# ButtonPanel.net
KiCad netlist of a schematic drawn in Altium Designer
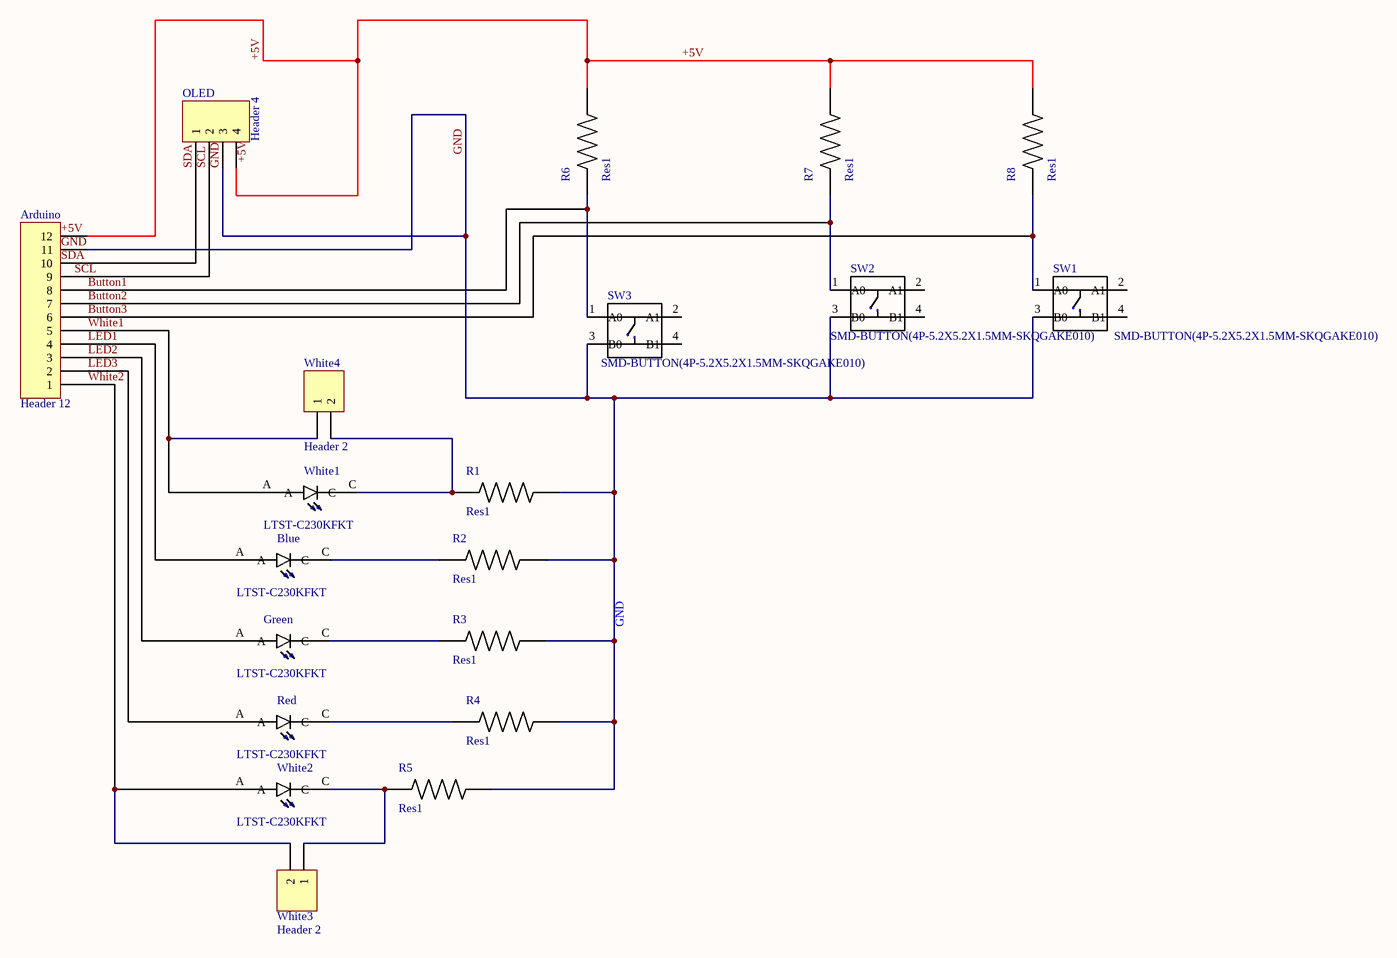
[diagram p0: ButtonPanel.SchDoc]

(export (version "E")
  (design (tool "Eeschema 10.0.6"))
  (components
    (comp (ref "Arduino")
      (value "Header 12")
      (footprint "HDR1X12")
      (description "Header, 12-Pin")
      (fields (field (name "PUBLISHER") "Altium Limited"))
      (libsource (lib "Miscellaneous Connectors") (part "Header 12"))
    )
    (comp (ref "Blue")
      (value "LTST-C230KFKT")
      (footprint "*LEDC3216X110_LTST-C230KFKT(Primary)")
      (description "LED; SMD; 1206; orange; 45-90mcd; 3.2x1.6x1.1mm; 130Â°; 2Ã·2.4V; 20mA")
      (fields (field (name "MF") "Lite-On Inc."))
      (libsource (lib "LTST-C230KFKT") (part "LTST-C230KFKT"))
    )
    (comp (ref "Green")
      (value "LTST-C230KFKT")
      (footprint "*LEDC3216X110_LTST-C230KFKT(Primary)")
      (description "LED; SMD; 1206; orange; 45-90mcd; 3.2x1.6x1.1mm; 130Â°; 2Ã·2.4V; 20mA")
      (fields (field (name "MF") "Lite-On Inc."))
      (libsource (lib "LTST-C230KFKT") (part "LTST-C230KFKT"))
    )
    (comp (ref "OLED")
      (value "Header 4")
      (footprint "HDR1X4")
      (description "Header, 4-Pin")
      (fields (field (name "PUBLISHER") "Altium Limited"))
      (libsource (lib "Miscellaneous Connectors") (part "Header 4"))
    )
    (comp (ref "R1")
      (value "Res1")
      (footprint "*RESC3116X65N")
      (description "RES SMD 330 OHM 0.5% 1/4W 1206")
      (fields (field (name "MF") "Yageo") (field (name "MP") "RT1206DRE07330RL"))
      (libsource (lib "RT1206DRE07330RL") (part "RT1206DRE07330RL"))
    )
    (comp (ref "R2")
      (value "Res1")
      (footprint "*RESC3116X65N")
      (description "RES SMD 330 OHM 0.5% 1/4W 1206")
      (fields (field (name "MF") "Yageo") (field (name "MP") "RT1206DRE07330RL"))
      (libsource (lib "RT1206DRE07330RL") (part "RT1206DRE07330RL"))
    )
    (comp (ref "R3")
      (value "Res1")
      (footprint "*RESC3116X65N")
      (description "RES SMD 330 OHM 0.5% 1/4W 1206")
      (fields (field (name "MF") "Yageo") (field (name "MP") "RT1206DRE07330RL"))
      (libsource (lib "RT1206DRE07330RL") (part "RT1206DRE07330RL"))
    )
    (comp (ref "R4")
      (value "Res1")
      (footprint "*RESC3116X65N")
      (description "RES SMD 330 OHM 0.5% 1/4W 1206")
      (fields (field (name "MF") "Yageo") (field (name "MP") "RT1206DRE07330RL"))
      (libsource (lib "RT1206DRE07330RL") (part "RT1206DRE07330RL"))
    )
    (comp (ref "R5")
      (value "Res1")
      (footprint "*RESC3116X65N")
      (description "RES SMD 330 OHM 0.5% 1/4W 1206")
      (fields (field (name "MF") "Yageo") (field (name "MP") "RT1206DRE07330RL"))
      (libsource (lib "RT1206DRE07330RL") (part "RT1206DRE07330RL"))
    )
    (comp (ref "R6")
      (value "Res1")
      (footprint "*RESC3116X65N")
      (description "RES SMD 10K OHM 0.5% 0.4W 1206")
      (fields (field (name "MF") "Vishay") (field (name "MP") "MCA1206MD1002DP500"))
      (libsource (lib "MCA1206MD1002DP500") (part "MCA1206MD1002DP500"))
    )
    (comp (ref "R7")
      (value "Res1")
      (footprint "*RESC3116X65N")
      (description "RES SMD 10K OHM 0.5% 0.4W 1206")
      (fields (field (name "MF") "Vishay") (field (name "MP") "MCA1206MD1002DP500"))
      (libsource (lib "MCA1206MD1002DP500") (part "MCA1206MD1002DP500"))
    )
    (comp (ref "R8")
      (value "Res1")
      (footprint "*RESC3116X65N")
      (description "RES SMD 10K OHM 0.5% 0.4W 1206")
      (fields (field (name "MF") "Vishay") (field (name "MP") "MCA1206MD1002DP500"))
      (libsource (lib "MCA1206MD1002DP500") (part "MCA1206MD1002DP500"))
    )
    (comp (ref "Red")
      (value "LTST-C230KFKT")
      (footprint "*LEDC3216X110_LTST-C230KFKT(Primary)")
      (description "LED; SMD; 1206; orange; 45-90mcd; 3.2x1.6x1.1mm; 130Â°; 2Ã·2.4V; 20mA")
      (fields (field (name "MF") "Lite-On Inc."))
      (libsource (lib "LTST-C230KFKT") (part "LTST-C230KFKT"))
    )
    (comp (ref "SW1")
      (value "SMD-BUTTON(4P-5.2X5.2X1.5MM-SKQGAKE010)")
      (footprint "*SW4-SMD-5.2X5.2X1.5MM")
      (description "Switch Tactile N.O. SPST Button Gull Wing 0.05A 12VDC 3.43N SMD T/R")
      (fields (field (name "MF") "ALPS") (field (name "MP") "SKQGAKE010"))
      (libsource (lib "SMD-BUTTON_4P-5.2X5.2X1.5MM-SKQGAKE010_") (part "SMD-BUTTON(4P-5.2X5.2X1.5MM-SKQGAKE010)"))
    )
    (comp (ref "SW2")
      (value "SMD-BUTTON(4P-5.2X5.2X1.5MM-SKQGAKE010)")
      (footprint "*SW4-SMD-5.2X5.2X1.5MM")
      (description "Switch Tactile N.O. SPST Button Gull Wing 0.05A 12VDC 3.43N SMD T/R")
      (fields (field (name "MF") "ALPS") (field (name "MP") "SKQGAKE010"))
      (libsource (lib "SMD-BUTTON_4P-5.2X5.2X1.5MM-SKQGAKE010_") (part "SMD-BUTTON(4P-5.2X5.2X1.5MM-SKQGAKE010)"))
    )
    (comp (ref "SW3")
      (value "SMD-BUTTON(4P-5.2X5.2X1.5MM-SKQGAKE010)")
      (footprint "*SW4-SMD-5.2X5.2X1.5MM")
      (description "Switch Tactile N.O. SPST Button Gull Wing 0.05A 12VDC 3.43N SMD T/R")
      (fields (field (name "MF") "ALPS") (field (name "MP") "SKQGAKE010"))
      (libsource (lib "SMD-BUTTON_4P-5.2X5.2X1.5MM-SKQGAKE010_") (part "SMD-BUTTON(4P-5.2X5.2X1.5MM-SKQGAKE010)"))
    )
    (comp (ref "White1")
      (value "LTST-C230KFKT")
      (footprint "*LEDC3216X110_LTST-C230KFKT(Primary)")
      (description "LED; SMD; 1206; orange; 45-90mcd; 3.2x1.6x1.1mm; 130Â°; 2Ã·2.4V; 20mA")
      (fields (field (name "MF") "Lite-On Inc."))
      (libsource (lib "LTST-C230KFKT") (part "LTST-C230KFKT"))
    )
    (comp (ref "White2")
      (value "LTST-C230KFKT")
      (footprint "*LEDC3216X110_LTST-C230KFKT(Primary)")
      (description "LED; SMD; 1206; orange; 45-90mcd; 3.2x1.6x1.1mm; 130Â°; 2Ã·2.4V; 20mA")
      (fields (field (name "MF") "Lite-On Inc."))
      (libsource (lib "LTST-C230KFKT") (part "LTST-C230KFKT"))
    )
    (comp (ref "White3")
      (value "Header 2")
      (footprint "HDR1X2")
      (description "Header, 2-Pin")
      (fields (field (name "PUBLISHER") "Altium Limited"))
      (libsource (lib "") (part "Header 2_1"))
    )
    (comp (ref "White4")
      (value "Header 2")
      (footprint "HDR1X2")
      (description "Header, 2-Pin")
      (fields (field (name "PUBLISHER") "Altium Limited"))
      (libsource (lib "Miscellaneous Connectors") (part "Header 2"))
    )
  )
  (nets
    (net (code "1") (name "/+5V") (class "Default")
      (node (ref "Arduino") (pin "12") (pinfunction "12_12") (pintype "passive"))
      (node (ref "OLED") (pin "4") (pinfunction "4_4") (pintype "passive"))
      (node (ref "R6") (pin "2") (pinfunction "2_2") (pintype "passive"))
      (node (ref "R7") (pin "2") (pinfunction "2_2") (pintype "passive"))
      (node (ref "R8") (pin "2") (pinfunction "2_2") (pintype "passive"))
    )
    (net (code "2") (name "/Button1") (class "Default")
      (node (ref "Arduino") (pin "8") (pinfunction "8_8") (pintype "passive"))
      (node (ref "R6") (pin "1") (pinfunction "1_1") (pintype "passive"))
      (node (ref "SW3") (pin "1") (pinfunction "A0_1") (pintype "bidirectional"))
    )
    (net (code "3") (name "/Button2") (class "Default")
      (node (ref "Arduino") (pin "7") (pinfunction "7_7") (pintype "passive"))
      (node (ref "R7") (pin "1") (pinfunction "1_1") (pintype "passive"))
      (node (ref "SW2") (pin "1") (pinfunction "A0_1") (pintype "bidirectional"))
    )
    (net (code "4") (name "/Button3") (class "Default")
      (node (ref "Arduino") (pin "6") (pinfunction "6_6") (pintype "passive"))
      (node (ref "R8") (pin "1") (pinfunction "1_1") (pintype "passive"))
      (node (ref "SW1") (pin "1") (pinfunction "A0_1") (pintype "bidirectional"))
    )
    (net (code "5") (name "/GND") (class "Default")
      (node (ref "Arduino") (pin "11") (pinfunction "11_11") (pintype "passive"))
      (node (ref "OLED") (pin "3") (pinfunction "3_3") (pintype "passive"))
      (node (ref "R1") (pin "2") (pinfunction "2_2") (pintype "passive"))
      (node (ref "R2") (pin "2") (pinfunction "2_2") (pintype "passive"))
      (node (ref "R3") (pin "2") (pinfunction "2_2") (pintype "passive"))
      (node (ref "R4") (pin "2") (pinfunction "2_2") (pintype "passive"))
      (node (ref "R5") (pin "2") (pinfunction "2_2") (pintype "passive"))
      (node (ref "SW1") (pin "3") (pinfunction "B0_3") (pintype "bidirectional"))
      (node (ref "SW2") (pin "3") (pinfunction "B0_3") (pintype "bidirectional"))
      (node (ref "SW3") (pin "3") (pinfunction "B0_3") (pintype "bidirectional"))
    )
    (net (code "6") (name "/LED1") (class "Default")
      (node (ref "Arduino") (pin "4") (pinfunction "4_4") (pintype "passive"))
      (node (ref "Blue") (pin "A") (pinfunction "A_A") (pintype "passive"))
    )
    (net (code "7") (name "/LED2") (class "Default")
      (node (ref "Arduino") (pin "3") (pinfunction "3_3") (pintype "passive"))
      (node (ref "Green") (pin "A") (pinfunction "A_A") (pintype "passive"))
    )
    (net (code "8") (name "/LED3") (class "Default")
      (node (ref "Arduino") (pin "2") (pinfunction "2_2") (pintype "passive"))
      (node (ref "Red") (pin "A") (pinfunction "A_A") (pintype "passive"))
    )
    (net (code "9") (name "/SCL") (class "Default")
      (node (ref "Arduino") (pin "9") (pinfunction "9_9") (pintype "passive"))
      (node (ref "OLED") (pin "2") (pinfunction "2_2") (pintype "passive"))
    )
    (net (code "10") (name "/SDA") (class "Default")
      (node (ref "Arduino") (pin "10") (pinfunction "10_10") (pintype "passive"))
      (node (ref "OLED") (pin "1") (pinfunction "1_1") (pintype "passive"))
    )
    (net (code "11") (name "/White1") (class "Default")
      (node (ref "Arduino") (pin "5") (pinfunction "5_5") (pintype "passive"))
      (node (ref "White1") (pin "A") (pinfunction "A_A") (pintype "passive"))
      (node (ref "White4") (pin "1") (pinfunction "1_1") (pintype "passive"))
    )
    (net (code "12") (name "/White2") (class "Default")
      (node (ref "Arduino") (pin "1") (pinfunction "1_1") (pintype "passive"))
      (node (ref "White2") (pin "A") (pinfunction "A_A") (pintype "passive"))
      (node (ref "White3") (pin "2") (pinfunction "2_2") (pintype "passive"))
    )
    (net (code "13") (name "Net-(Blue-PadC)") (class "Default")
      (node (ref "Blue") (pin "C") (pinfunction "C_C") (pintype "passive"))
      (node (ref "R2") (pin "1") (pinfunction "1_1") (pintype "passive"))
    )
    (net (code "14") (name "Net-(Green-PadC)") (class "Default")
      (node (ref "Green") (pin "C") (pinfunction "C_C") (pintype "passive"))
      (node (ref "R3") (pin "1") (pinfunction "1_1") (pintype "passive"))
    )
    (net (code "15") (name "Net-(R1-Pad1)") (class "Default")
      (node (ref "R1") (pin "1") (pinfunction "1_1") (pintype "passive"))
      (node (ref "White1") (pin "C") (pinfunction "C_C") (pintype "passive"))
      (node (ref "White4") (pin "2") (pinfunction "2_2") (pintype "passive"))
    )
    (net (code "16") (name "Net-(R4-Pad1)") (class "Default")
      (node (ref "R4") (pin "1") (pinfunction "1_1") (pintype "passive"))
      (node (ref "Red") (pin "C") (pinfunction "C_C") (pintype "passive"))
    )
    (net (code "17") (name "Net-(R5-Pad1)") (class "Default")
      (node (ref "R5") (pin "1") (pinfunction "1_1") (pintype "passive"))
      (node (ref "White2") (pin "C") (pinfunction "C_C") (pintype "passive"))
      (node (ref "White3") (pin "1") (pinfunction "1_1") (pintype "passive"))
    )
    (net (code "18") (name "unconnected-(SW1-A1-Pad2)") (class "Default")
      (node (ref "SW1") (pin "2") (pinfunction "A1_2") (pintype "bidirectional"))
    )
    (net (code "19") (name "unconnected-(SW1-B1-Pad4)") (class "Default")
      (node (ref "SW1") (pin "4") (pinfunction "B1_4") (pintype "bidirectional"))
    )
    (net (code "20") (name "unconnected-(SW2-A1-Pad2)") (class "Default")
      (node (ref "SW2") (pin "2") (pinfunction "A1_2") (pintype "bidirectional"))
    )
    (net (code "21") (name "unconnected-(SW2-B1-Pad4)") (class "Default")
      (node (ref "SW2") (pin "4") (pinfunction "B1_4") (pintype "bidirectional"))
    )
    (net (code "22") (name "unconnected-(SW3-A1-Pad2)") (class "Default")
      (node (ref "SW3") (pin "2") (pinfunction "A1_2") (pintype "bidirectional"))
    )
    (net (code "23") (name "unconnected-(SW3-B1-Pad4)") (class "Default")
      (node (ref "SW3") (pin "4") (pinfunction "B1_4") (pintype "bidirectional"))
    )
  )
)
